# CAN_Tranceiver.net
KiCad netlist of a schematic drawn in Altium Designer
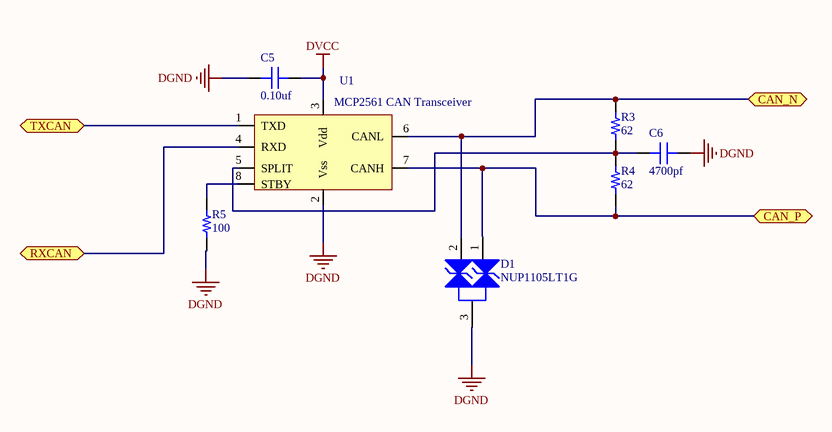
[diagram p0: CAN_Tranceiver.SchDoc]

(export (version "E")
  (design (tool "Eeschema 10.0.6"))
  (components
    (comp (ref "C5")
      (value "0.10uf")
      (footprint "CAP 0603/1608")
      (fields
        (field (name "Comment") "Capacitor MLCC 0.10uf 50V CAP 0603/1608")
        (field (name "CREATED_BY") "Nick Mah")
      )
      (libsource (lib "Altium-Lib") (part "Capacitor"))
    )
    (comp (ref "C6")
      (value "4700pf")
      (footprint "CAP 0603/1608")
      (fields
        (field (name "Comment") "Capacitor MLCC 4700pf 50V CAP 0603/1608")
        (field (name "CREATED_BY") "Nick Mah")
      )
      (libsource (lib "Altium-Lib") (part "Capacitor"))
    )
    (comp (ref "D1")
      (value "NUP1105LT1G")
      (footprint "SOT-23 (TO-236)")
      (description "ESD Protection Diode")
      (fields (field (name "POWER") "350W"))
      (libsource (lib "Altium-Lib") (part "NUP1105LT1G"))
    )
    (comp (ref "R3")
      (value "62")
      (footprint "RES 0603/1608")
      (fields
        (field (name "TOLERANCE") "5%")
        (field (name "POWER") "1/10W")
        (field (name "Comment") "Resistor 62 0603 1/10W 5%")
        (field (name "CREATED_BY") "Nick Mah")
      )
      (libsource (lib "Altium-Lib") (part "Resistor"))
    )
    (comp (ref "R4")
      (value "62")
      (footprint "RES 0603/1608")
      (fields
        (field (name "TOLERANCE") "5%")
        (field (name "POWER") "1/10W")
        (field (name "Comment") "Resistor 62 0603 1/10W 5%")
        (field (name "CREATED_BY") "Nick Mah")
      )
      (libsource (lib "Altium-Lib") (part "Resistor"))
    )
    (comp (ref "R5")
      (value "100")
      (footprint "RES 0603/1608")
      (fields
        (field (name "TOLERANCE") "10%")
        (field (name "POWER") "1/10W")
        (field (name "Comment") "Resistor 100 0603 1/10W 10%")
        (field (name "CREATED_BY") "Nick Mah")
      )
      (libsource (lib "Altium-Lib") (part "Resistor"))
    )
    (comp (ref "U1")
      (value "MCP2561 CAN Transceiver")
      (footprint "SOIC-8")
      (fields (field (name "MFRPARTNO") "MCP2561") (field (name "CREATED_BY") "Angel Delgado"))
      (libsource (lib "Altium-Lib") (part "MCP2561 CAN Transceiver"))
    )
  )
  (nets
    (net (code "1") (name "/CAN_N") (class "Default")
      (node (ref "D1") (pin "2") (pinfunction "K_2") (pintype "passive"))
      (node (ref "R3") (pin "1") (pinfunction "1_1") (pintype "passive"))
      (node (ref "U1") (pin "6") (pinfunction "CANL_6") (pintype "passive"))
    )
    (net (code "2") (name "/CAN_P") (class "Default")
      (node (ref "D1") (pin "1") (pinfunction "K_1") (pintype "passive"))
      (node (ref "R4") (pin "2") (pinfunction "2_2") (pintype "passive"))
      (node (ref "U1") (pin "7") (pinfunction "CANH_7") (pintype "passive"))
    )
    (net (code "3") (name "/RXCAN") (class "Default")
      (node (ref "U1") (pin "4") (pinfunction "RXD_4") (pintype "passive"))
    )
    (net (code "4") (name "/TXCAN") (class "Default")
      (node (ref "U1") (pin "1") (pinfunction "TXD_1") (pintype "passive"))
    )
    (net (code "5") (name "DGND") (class "Default")
      (node (ref "C5") (pin "1") (pinfunction "1_1") (pintype "passive"))
      (node (ref "C6") (pin "1") (pinfunction "1_1") (pintype "passive"))
      (node (ref "D1") (pin "3") (pinfunction "K_3") (pintype "passive"))
      (node (ref "R5") (pin "1") (pinfunction "1_1") (pintype "passive"))
      (node (ref "U1") (pin "2") (pinfunction "Vss_2") (pintype "passive"))
    )
    (net (code "6") (name "DVCC") (class "Default")
      (node (ref "C5") (pin "2") (pinfunction "2_2") (pintype "passive"))
      (node (ref "U1") (pin "3") (pinfunction "Vdd_3") (pintype "passive"))
    )
    (net (code "7") (name "Net-(U1-SPLIT)") (class "Default")
      (node (ref "C6") (pin "2") (pinfunction "2_2") (pintype "passive"))
      (node (ref "R3") (pin "2") (pinfunction "2_2") (pintype "passive"))
      (node (ref "R4") (pin "1") (pinfunction "1_1") (pintype "passive"))
      (node (ref "U1") (pin "5") (pinfunction "SPLIT_5") (pintype "passive"))
    )
    (net (code "8") (name "Net-(U1-STBY)") (class "Default")
      (node (ref "R5") (pin "2") (pinfunction "2_2") (pintype "passive"))
      (node (ref "U1") (pin "8") (pinfunction "STBY_8") (pintype "passive"))
    )
  )
)
